# BatuhanErbilBoostConverter.net
KiCad netlist of a schematic drawn in Altium Designer
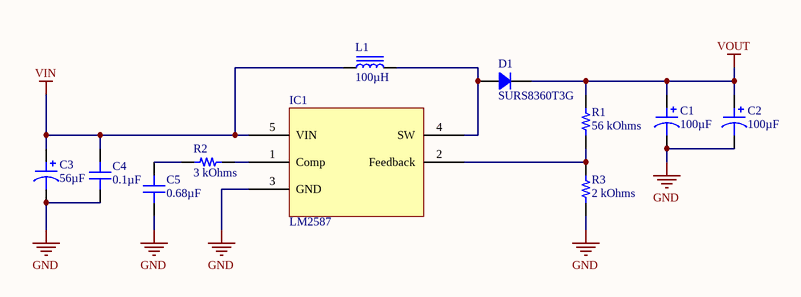
[diagram p0: BatuhanErbilBoostConverter.SchDoc]

(export (version "E")
  (design (tool "Eeschema 10.0.6"))
  (components
    (comp (ref "C1")
      (value "100µF")
      (footprint "CAP ALSMD 8.3MM H10.5MM")
      (description "CAP ALUM 100UF 20% 50V SMD")
      (fields
        (field (name "PART NUMBER") "EEE-FK1H101P")
        (field (name "MANUFACTURER") "Panasonic Electronic Components")
      )
      (libsource (lib "Celestial Altium Library - altium_library") (part "Polarised Capacitor"))
    )
    (comp (ref "C2")
      (value "100µF")
      (footprint "CAP ALSMD 8.3MM H10.5MM")
      (description "CAP ALUM 100UF 20% 50V SMD")
      (fields
        (field (name "PART NUMBER") "EEE-FK1H101P")
        (field (name "MANUFACTURER") "Panasonic Electronic Components")
      )
      (libsource (lib "Celestial Altium Library - altium_library") (part "Polarised Capacitor"))
    )
    (comp (ref "C3")
      (value "56µF")
      (footprint "CAP ALSMD 6.6MM H7.7MM")
      (description "CAP ALUM 56UF 20% 35V SMD")
      (fields (field (name "PART NUMBER") "UWD1V560MCL1GS") (field (name "MANUFACTURER") "Nichicon"))
      (libsource (lib "Celestial Altium Library - altium_library") (part "Polarised Capacitor"))
    )
    (comp (ref "C4")
      (value "0.1µF")
      (footprint "CAP 0805_2012")
      (description "CAP CER 0.1UF 50V X7R 0805")
      (fields (field (name "PART NUMBER") "CC0805JRX7R9BB104") (field (name "MANUFACTURER") "Yageo"))
      (libsource (lib "Celestial Altium Library - altium_library") (part "Capacitor"))
    )
    (comp (ref "C5")
      (value "0.68µF")
      (footprint "CAP 0805_2012")
      (description "CAP CER 0.68UF 50V X7R 0805")
      (fields (field (name "PART NUMBER") "C0805C684K5RACAUTO") (field (name "MANUFACTURER") "KEMET"))
      (libsource (lib "Celestial Altium Library - altium_library") (part "Capacitor"))
    )
    (comp (ref "D1")
      (value "SURS8360T3G")
      (footprint "DO214AB SMC")
      (description "DIODE GEN PURP 600V 3A SMC")
      (fields (field (name "MANUFACTURER") "ON Semiconductor"))
      (libsource (lib "Celestial Altium Library - altium_library") (part "Diode"))
    )
    (comp (ref "IC1")
      (value "LM2587")
      (footprint "D2PAK")
      (description "Boost Converter")
      (libsource (lib "AltiumConverter") (part "LM2587"))
    )
    (comp (ref "L1")
      (value "100µH")
      (footprint "7447070")
      (description "FIXED IND 100UH 2.1A 150MOHM SMD")
      (fields (field (name "PART NUMBER") "SRR1280-101M") (field (name "MANUFACTURER") "Bourns Inc."))
      (libsource (lib "Celestial Altium Library - altium_library") (part "Inductor"))
    )
    (comp (ref "R1")
      (value "56 kOhms")
      (footprint "RES 0805_2012")
      (description "RES 56K OHM 5% 1/8W 0805")
      (fields
        (field (name "PART NUMBER") "RMCF0805JT56K0")
        (field (name "MANUFACTURER") "Stackpole Electronics Inc")
      )
      (libsource (lib "Celestial Altium Library - altium_library") (part "Resistor"))
    )
    (comp (ref "R2")
      (value "3 kOhms")
      (footprint "RES 0805_2012")
      (description "RES SMD 3K OHM 1% 1/8W 0805")
      (fields
        (field (name "PART NUMBER") "ERJ-6ENF3001V")
        (field (name "MANUFACTURER") "Panasonic Electronic Components")
      )
      (libsource (lib "Celestial Altium Library - altium_library") (part "Resistor"))
    )
    (comp (ref "R3")
      (value "2 kOhms")
      (footprint "RES 0805_2012")
      (description "RES SMD 2K OHM 1% 1/8W 0805")
      (fields (field (name "PART NUMBER") "AC0805FR-072KL") (field (name "MANUFACTURER") "Yageo"))
      (libsource (lib "Celestial Altium Library - altium_library") (part "Resistor"))
    )
  )
  (nets
    (net (code "1") (name "GND") (class "Default")
      (node (ref "C1") (pin "2") (pinfunction "2_2") (pintype "passive"))
      (node (ref "C2") (pin "2") (pinfunction "2_2") (pintype "passive"))
      (node (ref "C3") (pin "2") (pinfunction "2_2") (pintype "passive"))
      (node (ref "C4") (pin "1") (pinfunction "1_1") (pintype "passive"))
      (node (ref "C5") (pin "1") (pinfunction "1_1") (pintype "passive"))
      (node (ref "IC1") (pin "3") (pinfunction "GND_3") (pintype "passive"))
      (node (ref "R3") (pin "1") (pinfunction "1_1") (pintype "passive"))
    )
    (net (code "2") (name "Net-(C5-Pad2)") (class "Default")
      (node (ref "C5") (pin "2") (pinfunction "2_2") (pintype "passive"))
      (node (ref "R2") (pin "1") (pinfunction "1_1") (pintype "passive"))
    )
    (net (code "3") (name "Net-(IC1-Comp)") (class "Default")
      (node (ref "IC1") (pin "1") (pinfunction "Comp_1") (pintype "passive"))
      (node (ref "R2") (pin "2") (pinfunction "2_2") (pintype "passive"))
    )
    (net (code "4") (name "Net-(IC1-Feedback)") (class "Default")
      (node (ref "IC1") (pin "2") (pinfunction "Feedback_2") (pintype "passive"))
      (node (ref "R1") (pin "1") (pinfunction "1_1") (pintype "passive"))
      (node (ref "R3") (pin "2") (pinfunction "2_2") (pintype "passive"))
    )
    (net (code "5") (name "Net-(IC1-SW)") (class "Default")
      (node (ref "D1") (pin "1") (pinfunction "1_1") (pintype "passive"))
      (node (ref "IC1") (pin "4") (pinfunction "SW_4") (pintype "passive"))
      (node (ref "L1") (pin "2") (pinfunction "2_2") (pintype "passive"))
    )
    (net (code "6") (name "VIN") (class "Default")
      (node (ref "C3") (pin "1") (pinfunction "1_1") (pintype "passive"))
      (node (ref "C4") (pin "2") (pinfunction "2_2") (pintype "passive"))
      (node (ref "IC1") (pin "5") (pinfunction "VIN_5") (pintype "passive"))
      (node (ref "L1") (pin "1") (pinfunction "1_1") (pintype "passive"))
    )
    (net (code "7") (name "VOUT") (class "Default")
      (node (ref "C1") (pin "1") (pinfunction "1_1") (pintype "passive"))
      (node (ref "C2") (pin "1") (pinfunction "1_1") (pintype "passive"))
      (node (ref "D1") (pin "2") (pinfunction "2_2") (pintype "passive"))
      (node (ref "R1") (pin "2") (pinfunction "2_2") (pintype "passive"))
    )
  )
)
